# Sheet1.net
KiCad netlist of a schematic drawn in Altium Designer
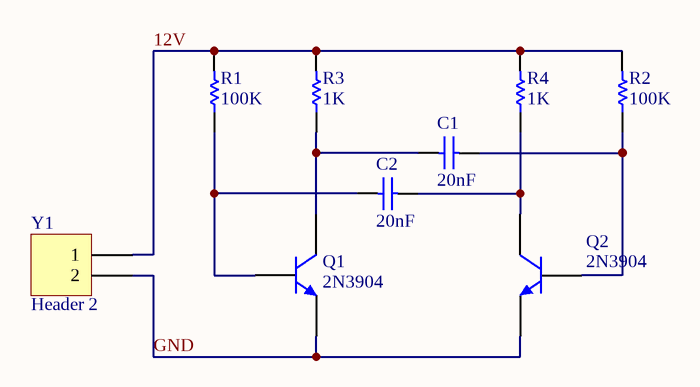
[diagram p0: Sheet1.SchDoc]

(export (version "E")
  (design (tool "Eeschema 10.0.6"))
  (components
    (comp (ref "C1")
      (value "20nF")
      (footprint "RAD-0.3")
      (description "Capacitor")
      (fields (field (name "PUBLISHER") "Altium Limited"))
      (libsource (lib "Miscellaneous Devices") (part "Cap"))
    )
    (comp (ref "C2")
      (value "20nF")
      (footprint "RAD-0.3")
      (description "Capacitor")
      (fields (field (name "PUBLISHER") "Altium Limited"))
      (libsource (lib "Miscellaneous Devices") (part "Cap"))
    )
    (comp (ref "Q1")
      (value "2N3904")
      (footprint "TO-92A")
      (description "NPN General Purpose Amplifier")
      (fields (field (name "PUBLISHER") "Altium Limited"))
      (libsource (lib "Miscellaneous Devices") (part "2N3904"))
    )
    (comp (ref "Q2")
      (value "2N3904")
      (footprint "TO-92A")
      (description "NPN General Purpose Amplifier")
      (fields (field (name "PUBLISHER") "Altium Limited"))
      (libsource (lib "Miscellaneous Devices") (part "2N3904"))
    )
    (comp (ref "R1")
      (value "100K")
      (footprint "AXIAL-0.3")
      (description "Resistor")
      (fields (field (name "PUBLISHER") "Altium Limited"))
      (libsource (lib "Miscellaneous Devices") (part "Res1"))
    )
    (comp (ref "R2")
      (value "100K")
      (footprint "AXIAL-0.3")
      (description "Resistor")
      (fields (field (name "PUBLISHER") "Altium Limited"))
      (libsource (lib "Miscellaneous Devices") (part "Res1"))
    )
    (comp (ref "R3")
      (value "1K")
      (footprint "AXIAL-0.3")
      (description "Resistor")
      (fields (field (name "PUBLISHER") "Altium Limited"))
      (libsource (lib "Miscellaneous Devices") (part "Res1"))
    )
    (comp (ref "R4")
      (value "1K")
      (footprint "AXIAL-0.3")
      (description "Resistor")
      (fields (field (name "PUBLISHER") "Altium Limited"))
      (libsource (lib "Miscellaneous Devices") (part "Res1"))
    )
    (comp (ref "Y1")
      (value "Header 2")
      (footprint "HDR1X2")
      (description "Header, 2-Pin")
      (fields (field (name "PUBLISHER") "Altium Limited"))
      (libsource (lib "Miscellaneous Connectors") (part "Header 2"))
    )
  )
  (nets
    (net (code "1") (name "/12V") (class "Default")
      (node (ref "R1") (pin "2") (pinfunction "2_2") (pintype "passive"))
      (node (ref "R2") (pin "2") (pinfunction "2_2") (pintype "passive"))
      (node (ref "R3") (pin "2") (pinfunction "2_2") (pintype "passive"))
      (node (ref "R4") (pin "2") (pinfunction "2_2") (pintype "passive"))
      (node (ref "Y1") (pin "1") (pinfunction "1_1") (pintype "passive"))
    )
    (net (code "2") (name "/GND") (class "Default")
      (node (ref "Q1") (pin "1") (pinfunction "E_1") (pintype "passive"))
      (node (ref "Q2") (pin "1") (pinfunction "E_1") (pintype "passive"))
      (node (ref "Y1") (pin "2") (pinfunction "2_2") (pintype "passive"))
    )
    (net (code "3") (name "Net-(Q1-B)") (class "Default")
      (node (ref "C2") (pin "1") (pinfunction "1_1") (pintype "passive"))
      (node (ref "Q1") (pin "2") (pinfunction "B_2") (pintype "passive"))
      (node (ref "R1") (pin "1") (pinfunction "1_1") (pintype "passive"))
    )
    (net (code "4") (name "Net-(Q1-C)") (class "Default")
      (node (ref "C1") (pin "1") (pinfunction "1_1") (pintype "passive"))
      (node (ref "Q1") (pin "3") (pinfunction "C_3") (pintype "passive"))
      (node (ref "R3") (pin "1") (pinfunction "1_1") (pintype "passive"))
    )
    (net (code "5") (name "Net-(Q2-B)") (class "Default")
      (node (ref "C1") (pin "2") (pinfunction "2_2") (pintype "passive"))
      (node (ref "Q2") (pin "2") (pinfunction "B_2") (pintype "passive"))
      (node (ref "R2") (pin "1") (pinfunction "1_1") (pintype "passive"))
    )
    (net (code "6") (name "Net-(Q2-C)") (class "Default")
      (node (ref "C2") (pin "2") (pinfunction "2_2") (pintype "passive"))
      (node (ref "Q2") (pin "3") (pinfunction "C_3") (pintype "passive"))
      (node (ref "R4") (pin "1") (pinfunction "1_1") (pintype "passive"))
    )
  )
)
